# LickDetector_Flex.net
KiCad netlist of a schematic drawn in EAGLE
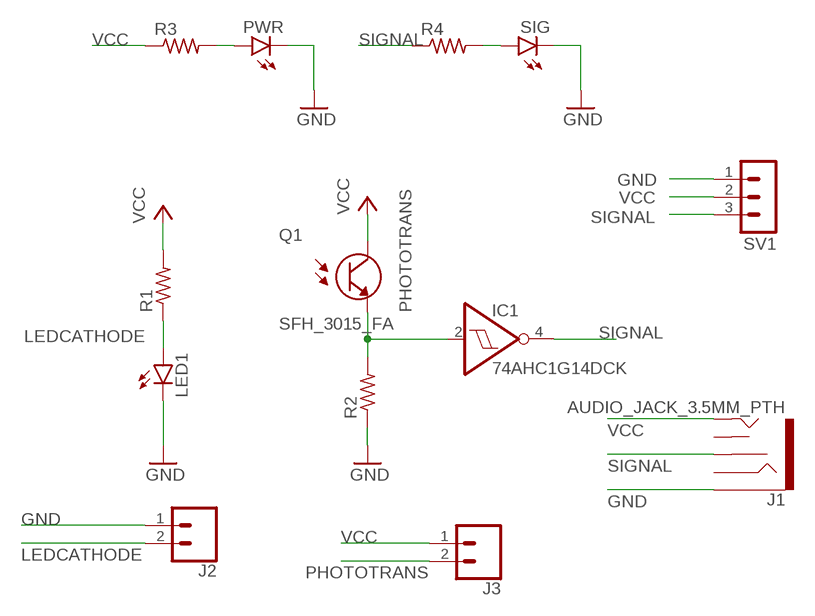
[diagram p0: schematic, sheet 1]

(export (version "E")
  (design (tool "Eeschema 10.0.6"))
  (components
    (comp (ref "IC1")
      (value "74AHC1G14DCK")
      (footprint "eagle-import:SC70-5")
      (libsource (lib "eagle-import") (part "741G14DCKAHC"))
    )
    (comp (ref "J1")
      (value "AUDIO_JACK_3.5MM_PTH")
      (footprint "eagle-import:AUDIO-JACK")
      (libsource (lib "eagle-import") (part "AUDIO_JACK_3.5MM_PTH"))
    )
    (comp (ref "J2")
      (value "CONN_02")
      (footprint "eagle-import:1X02")
      (libsource (lib "eagle-import") (part "CONN_02"))
    )
    (comp (ref "J3")
      (value "CONN_02")
      (footprint "eagle-import:1X02")
      (libsource (lib "eagle-import") (part "CONN_02"))
    )
    (comp (ref "LED1")
      (value "LEDCHIPLED_1206")
      (footprint "eagle-import:CHIPLED_1206")
      (libsource (lib "eagle-import") (part "LEDCHIPLED_1206"))
    )
    (comp (ref "PWR")
      (value "LEDCHIP-LED0603")
      (footprint "eagle-import:CHIP-LED0603")
      (libsource (lib "eagle-import") (part "LEDCHIP-LED0603"))
    )
    (comp (ref "Q1")
      (value "SFH_3015_FA")
      (footprint "eagle-import:XDCR_SFH_3015_FA")
      (fields
        (field (name "DIGI-KEY_PART_NUMBER") "475-2914-1-ND")
        (field (name "MF") "OSRAM Opto")
        (field (name "MP") "SFH 3015 FA")
      )
      (libsource (lib "eagle-import") (part "SFH_3015_FA"))
    )
    (comp (ref "R1")
      (value "R-US_R0603")
      (footprint "eagle-import:R0603")
      (libsource (lib "eagle-import") (part "R-US_R0603"))
    )
    (comp (ref "R2")
      (value "R-US_R0603")
      (footprint "eagle-import:R0603")
      (libsource (lib "eagle-import") (part "R-US_R0603"))
    )
    (comp (ref "R3")
      (value "R-US_R0603")
      (footprint "eagle-import:R0603")
      (libsource (lib "eagle-import") (part "R-US_R0603"))
    )
    (comp (ref "R4")
      (value "R-US_R0603")
      (footprint "eagle-import:R0603")
      (libsource (lib "eagle-import") (part "R-US_R0603"))
    )
    (comp (ref "SIG")
      (value "LEDCHIP-LED0603")
      (footprint "eagle-import:CHIP-LED0603")
      (libsource (lib "eagle-import") (part "LEDCHIP-LED0603"))
    )
    (comp (ref "SV1")
      (value "MA03-1")
      (footprint "eagle-import:MA03-1")
      (libsource (lib "eagle-import") (part "MA03-1"))
    )
  )
  (nets
    (net (code "1") (name "/LEDCATHODE") (class "Default")
      (node (ref "J2") (pin "2") (pinfunction "2_2") (pintype "passive"))
      (node (ref "LED1") (pin "A") (pinfunction "A_A") (pintype "passive"))
      (node (ref "R1") (pin "1") (pinfunction "1_1") (pintype "passive"))
    )
    (net (code "2") (name "/PHOTOTRANS") (class "Default")
      (node (ref "IC1") (pin "2") (pinfunction "I_2") (pintype "input"))
      (node (ref "J3") (pin "2") (pinfunction "2_2") (pintype "passive"))
      (node (ref "Q1") (pin "1") (pinfunction "E_1") (pintype "passive"))
      (node (ref "R2") (pin "2") (pinfunction "2_2") (pintype "passive"))
    )
    (net (code "3") (name "/SIGNAL") (class "Default")
      (node (ref "IC1") (pin "4") (pinfunction "O_4") (pintype "output"))
      (node (ref "J1") (pin "RSH") (pinfunction "RSH_RSH") (pintype "bidirectional"))
      (node (ref "R4") (pin "1") (pinfunction "1_1") (pintype "passive"))
      (node (ref "SV1") (pin "3") (pinfunction "3_3") (pintype "passive"))
    )
    (net (code "4") (name "GND") (class "Default")
      (node (ref "J1") (pin "SLEEVE") (pinfunction "SLEEVE_SLEEVE") (pintype "bidirectional"))
      (node (ref "J2") (pin "1") (pinfunction "1_1") (pintype "passive"))
      (node (ref "LED1") (pin "C") (pinfunction "C_C") (pintype "passive"))
      (node (ref "PWR") (pin "C") (pinfunction "C_C") (pintype "passive"))
      (node (ref "R2") (pin "1") (pinfunction "1_1") (pintype "passive"))
      (node (ref "SIG") (pin "C") (pinfunction "C_C") (pintype "passive"))
      (node (ref "SV1") (pin "1") (pinfunction "1_1") (pintype "passive"))
    )
    (net (code "5") (name "Net-(PWR-PadA)") (class "Default")
      (node (ref "PWR") (pin "A") (pinfunction "A_A") (pintype "passive"))
      (node (ref "R3") (pin "2") (pinfunction "2_2") (pintype "passive"))
    )
    (net (code "6") (name "Net-(R4-Pad2)") (class "Default")
      (node (ref "R4") (pin "2") (pinfunction "2_2") (pintype "passive"))
      (node (ref "SIG") (pin "A") (pinfunction "A_A") (pintype "passive"))
    )
    (net (code "7") (name "VCC") (class "Default")
      (node (ref "J1") (pin "TIP") (pinfunction "TIP_TIP") (pintype "bidirectional"))
      (node (ref "J3") (pin "1") (pinfunction "1_1") (pintype "passive"))
      (node (ref "Q1") (pin "2") (pinfunction "C_2") (pintype "passive"))
      (node (ref "R1") (pin "2") (pinfunction "2_2") (pintype "passive"))
      (node (ref "R3") (pin "1") (pinfunction "1_1") (pintype "passive"))
      (node (ref "SV1") (pin "2") (pinfunction "2_2") (pintype "passive"))
    )
    (net (code "8") (name "unconnected-(J1-PadRING)") (class "Default")
      (node (ref "J1") (pin "RING") (pinfunction "RING_RING") (pintype "bidirectional"))
    )
    (net (code "9") (name "unconnected-(J1-PadTSH)") (class "Default")
      (node (ref "J1") (pin "TSH") (pinfunction "TSH_TSH") (pintype "bidirectional"))
    )
  )
)
